# Markovic_Mario.net
KiCad netlist of a schematic drawn in Altium Designer
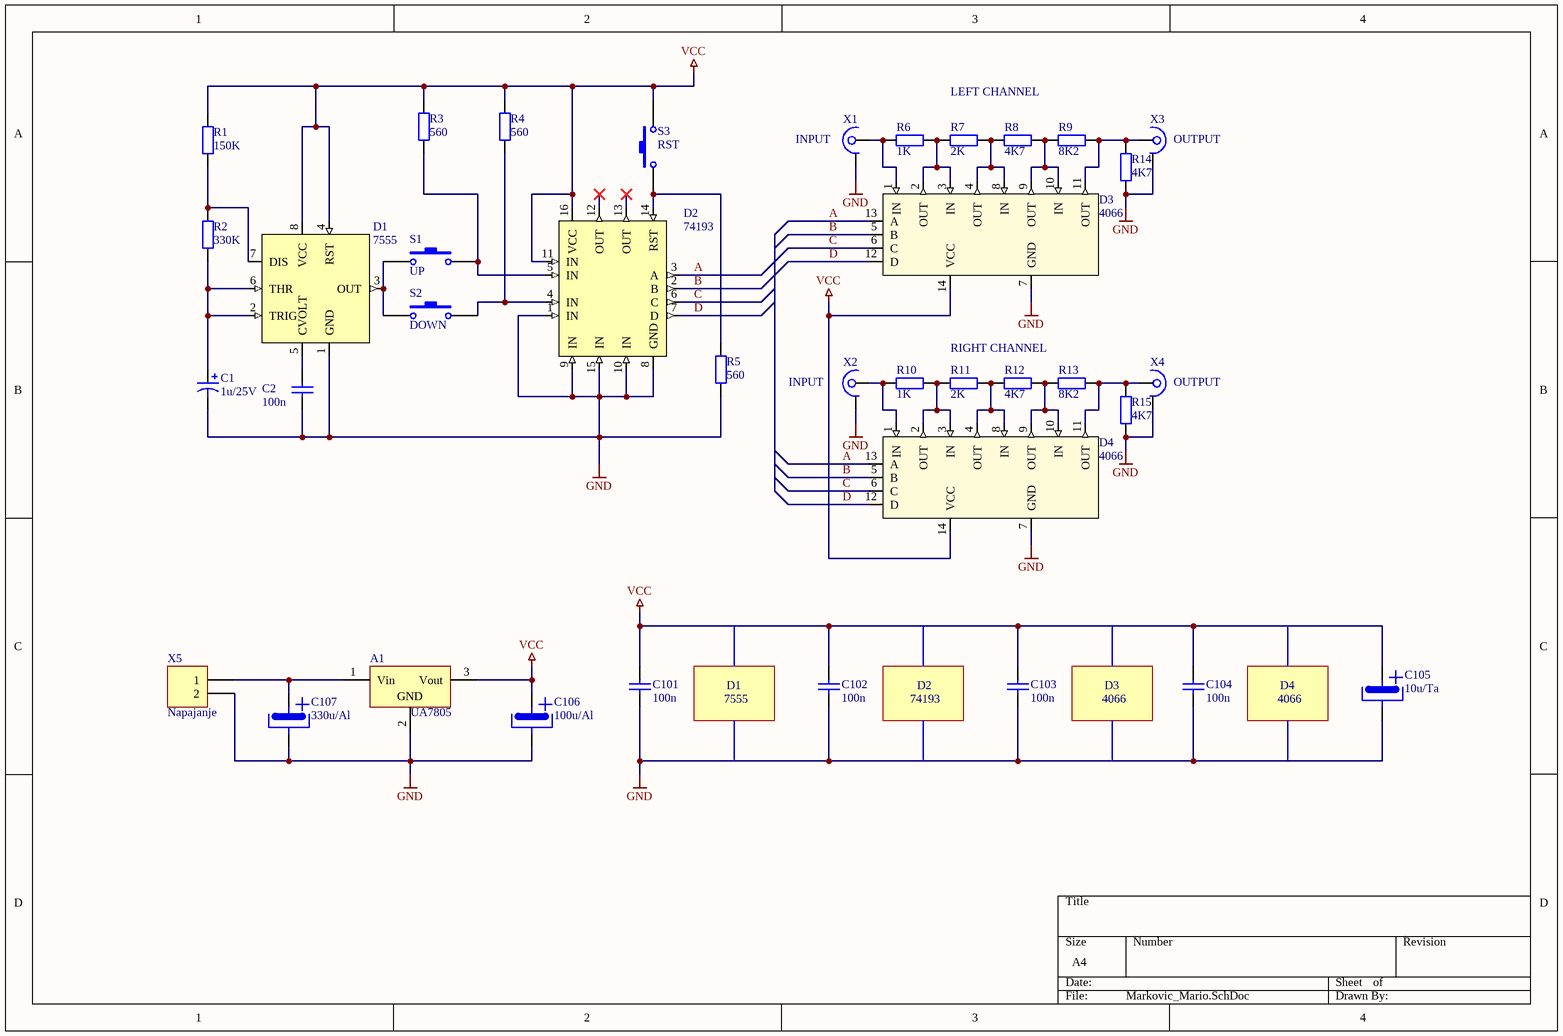
[diagram p0: Markovic_Mario.SchDoc]

(export (version "E")
  (design (tool "Eeschema 10.0.6"))
  (components
    (comp (ref "A1")
      (value "UA7805")
      (footprint "TO-220AB")
      (description "Voltage Regulator")
      (libsource (lib "Miscellaneous Devices") (part "Volt Reg"))
    )
    (comp (ref "C1")
      (value "1u/25V")
      (footprint "RB7.6-15")
      (description "Polarized Capacitor (Radial)")
      (libsource (lib "Miscellaneous Devices") (part "Cap Pol1"))
    )
    (comp (ref "C2")
      (value "100n")
      (footprint "RAD-0.3")
      (description "Capacitor")
      (libsource (lib "Miscellaneous Devices") (part "Cap"))
    )
    (comp (ref "C101")
      (value "100n")
      (footprint "RAD-0.3")
      (description "Capacitor")
      (libsource (lib "Miscellaneous Devices") (part "Cap"))
    )
    (comp (ref "C102")
      (value "100n")
      (footprint "RAD-0.3")
      (description "Capacitor")
      (libsource (lib "Miscellaneous Devices") (part "Cap"))
    )
    (comp (ref "C103")
      (value "100n")
      (footprint "RAD-0.3")
      (description "Capacitor")
      (libsource (lib "Miscellaneous Devices") (part "Cap"))
    )
    (comp (ref "C104")
      (value "100n")
      (footprint "RAD-0.3")
      (description "Capacitor")
      (libsource (lib "Miscellaneous Devices") (part "Cap"))
    )
    (comp (ref "C105")
      (value "10u/Ta")
      (footprint "RB7.6-15")
      (libsource (lib "Markovic_Mario") (part "Elektrolitski kondenzator"))
    )
    (comp (ref "C106")
      (value "100u/Al")
      (footprint "RB7.6-15")
      (libsource (lib "Markovic_Mario") (part "Elektrolitski kondenzator"))
    )
    (comp (ref "C107")
      (value "330u/Al")
      (footprint "RB7.6-15")
      (libsource (lib "Markovic_Mario") (part "Elektrolitski kondenzator"))
    )
    (comp (ref "D1") (value "7555") (footprint "DIP-8") (libsource (lib "Markovic_Mario") (part "7555")))
    (comp (ref "D2") (value "74193") (footprint "DIP-16") (libsource (lib "Markovic_Mario") (part "74193")))
    (comp (ref "D3") (value "4066") (footprint "DIP-14") (libsource (lib "Markovic_Mario") (part "4066")))
    (comp (ref "D4") (value "4066") (footprint "DIP-14") (libsource (lib "Markovic_Mario") (part "4066")))
    (comp (ref "R1")
      (value "150K")
      (footprint "AXIAL-0.4")
      (description "Resistor")
      (libsource (lib "") (part "Res2_1"))
    )
    (comp (ref "R2")
      (value "330K")
      (footprint "AXIAL-0.4")
      (description "Resistor")
      (libsource (lib "Miscellaneous Devices") (part "Res2"))
    )
    (comp (ref "R3")
      (value "560")
      (footprint "AXIAL-0.4")
      (description "Resistor")
      (libsource (lib "Miscellaneous Devices") (part "Res2"))
    )
    (comp (ref "R4")
      (value "560")
      (footprint "AXIAL-0.4")
      (description "Resistor")
      (libsource (lib "Miscellaneous Devices") (part "Res2"))
    )
    (comp (ref "R5")
      (value "560")
      (footprint "AXIAL-0.4")
      (description "Resistor")
      (libsource (lib "Miscellaneous Devices") (part "Res2"))
    )
    (comp (ref "R6")
      (value "1K")
      (footprint "AXIAL-0.4")
      (description "Resistor")
      (libsource (lib "") (part "Res2_2"))
    )
    (comp (ref "R7")
      (value "2K")
      (footprint "AXIAL-0.4")
      (description "Resistor")
      (libsource (lib "") (part "Res2_2"))
    )
    (comp (ref "R8")
      (value "4K7")
      (footprint "AXIAL-0.4")
      (description "Resistor")
      (libsource (lib "") (part "Res2_2"))
    )
    (comp (ref "R9")
      (value "8K2")
      (footprint "AXIAL-0.4")
      (description "Resistor")
      (libsource (lib "") (part "Res2_2"))
    )
    (comp (ref "R10")
      (value "1K")
      (footprint "AXIAL-0.4")
      (description "Resistor")
      (libsource (lib "") (part "Res2_2"))
    )
    (comp (ref "R11")
      (value "2K")
      (footprint "AXIAL-0.4")
      (description "Resistor")
      (libsource (lib "") (part "Res2_2"))
    )
    (comp (ref "R12")
      (value "4K7")
      (footprint "AXIAL-0.4")
      (description "Resistor")
      (libsource (lib "") (part "Res2_2"))
    )
    (comp (ref "R13")
      (value "8K2")
      (footprint "AXIAL-0.4")
      (description "Resistor")
      (libsource (lib "") (part "Res2_2"))
    )
    (comp (ref "R14")
      (value "4K7")
      (footprint "AXIAL-0.4")
      (description "Resistor")
      (libsource (lib "Miscellaneous Devices") (part "Res2"))
    )
    (comp (ref "R15")
      (value "4K7")
      (footprint "AXIAL-0.4")
      (description "Resistor")
      (libsource (lib "Miscellaneous Devices") (part "Res2"))
    )
    (comp (ref "S1")
      (value "UP")
      (footprint "SWITCH")
      (description "Switch")
      (libsource (lib "Miscellaneous Devices") (part "SW-PB"))
    )
    (comp (ref "S2")
      (value "DOWN")
      (footprint "SWITCH")
      (description "Switch")
      (libsource (lib "Miscellaneous Devices") (part "SW-PB"))
    )
    (comp (ref "S3")
      (value "RST")
      (footprint "SWITCH")
      (description "Switch")
      (libsource (lib "Miscellaneous Devices") (part "SW-PB"))
    )
    (comp (ref "X1") (value "INPUT") (footprint "JACK") (libsource (lib "Markovic_Mario") (part "Konektor")))
    (comp (ref "X2") (value "INPUT") (footprint "JACK") (libsource (lib "Markovic_Mario") (part "Konektor")))
    (comp (ref "X3") (value "OUTPUT") (footprint "JACK") (libsource (lib "") (part "Konektor_1")))
    (comp (ref "X4") (value "OUTPUT") (footprint "JACK") (libsource (lib "") (part "Konektor_1")))
    (comp (ref "X5")
      (value "Napajanje")
      (footprint "BAT-2")
      (description "Header, 2-Pin")
      (libsource (lib "Miscellaneous Connectors") (part "Header 2"))
    )
  )
  (nets
    (net (code "1") (name "/A") (class "Default")
      (node (ref "D2") (pin "3") (pinfunction "A_3") (pintype "output"))
      (node (ref "D3") (pin "13") (pinfunction "A_13") (pintype "passive"))
      (node (ref "D4") (pin "13") (pinfunction "A_13") (pintype "passive"))
    )
    (net (code "2") (name "/B") (class "Default")
      (node (ref "D2") (pin "2") (pinfunction "B_2") (pintype "output"))
      (node (ref "D3") (pin "5") (pinfunction "B_5") (pintype "passive"))
      (node (ref "D4") (pin "5") (pinfunction "B_5") (pintype "passive"))
    )
    (net (code "3") (name "/C") (class "Default")
      (node (ref "D2") (pin "6") (pinfunction "C_6") (pintype "output"))
      (node (ref "D3") (pin "6") (pinfunction "C_6") (pintype "passive"))
      (node (ref "D4") (pin "6") (pinfunction "C_6") (pintype "passive"))
    )
    (net (code "4") (name "/D") (class "Default")
      (node (ref "D2") (pin "7") (pinfunction "D_7") (pintype "output"))
      (node (ref "D3") (pin "12") (pinfunction "D_12") (pintype "passive"))
      (node (ref "D4") (pin "12") (pinfunction "D_12") (pintype "passive"))
    )
    (net (code "5") (name "GND") (class "Default")
      (node (ref "A1") (pin "2") (pinfunction "GND_2") (pintype "passive"))
      (node (ref "C1") (pin "2") (pinfunction "2_2") (pintype "passive"))
      (node (ref "C101") (pin "1") (pinfunction "1_1") (pintype "passive"))
      (node (ref "C102") (pin "1") (pinfunction "1_1") (pintype "passive"))
      (node (ref "C103") (pin "1") (pinfunction "1_1") (pintype "passive"))
      (node (ref "C104") (pin "1") (pinfunction "1_1") (pintype "passive"))
      (node (ref "C105") (pin "2") (pinfunction "2_2") (pintype "passive"))
      (node (ref "C106") (pin "2") (pinfunction "2_2") (pintype "passive"))
      (node (ref "C107") (pin "2") (pinfunction "2_2") (pintype "passive"))
      (node (ref "C2") (pin "1") (pinfunction "1_1") (pintype "passive"))
      (node (ref "D1") (pin "1") (pinfunction "GND_1") (pintype "power_in"))
      (node (ref "D2") (pin "1") (pinfunction "IN_1") (pintype "input"))
      (node (ref "D2") (pin "10") (pinfunction "IN_10") (pintype "input"))
      (node (ref "D2") (pin "15") (pinfunction "IN_15") (pintype "input"))
      (node (ref "D2") (pin "8") (pinfunction "GND_8") (pintype "power_in"))
      (node (ref "D2") (pin "9") (pinfunction "IN_9") (pintype "input"))
      (node (ref "D3") (pin "7") (pinfunction "GND_7") (pintype "power_in"))
      (node (ref "D4") (pin "7") (pinfunction "GND_7") (pintype "power_in"))
      (node (ref "R14") (pin "1") (pinfunction "1_1") (pintype "passive"))
      (node (ref "R15") (pin "1") (pinfunction "1_1") (pintype "passive"))
      (node (ref "R5") (pin "1") (pinfunction "1_1") (pintype "passive"))
      (node (ref "X1") (pin "2") (pinfunction "2_2") (pintype "passive"))
      (node (ref "X2") (pin "2") (pinfunction "2_2") (pintype "passive"))
      (node (ref "X3") (pin "2") (pinfunction "2_2") (pintype "passive"))
      (node (ref "X4") (pin "2") (pinfunction "2_2") (pintype "passive"))
      (node (ref "X5") (pin "2") (pinfunction "2_2") (pintype "passive"))
    )
    (net (code "6") (name "Net-(A1-Vin)") (class "Default")
      (node (ref "A1") (pin "1") (pinfunction "Vin_1") (pintype "passive"))
      (node (ref "C107") (pin "1") (pinfunction "1_1") (pintype "passive"))
      (node (ref "X5") (pin "1") (pinfunction "1_1") (pintype "passive"))
    )
    (net (code "7") (name "Net-(D1-CVOLT)") (class "Default")
      (node (ref "C2") (pin "2") (pinfunction "2_2") (pintype "passive"))
      (node (ref "D1") (pin "5") (pinfunction "CVOLT_5") (pintype "passive"))
    )
    (net (code "8") (name "Net-(D1-DIS)") (class "Default")
      (node (ref "D1") (pin "7") (pinfunction "DIS_7") (pintype "passive"))
      (node (ref "R1") (pin "2") (pinfunction "2_2") (pintype "passive"))
      (node (ref "R2") (pin "2") (pinfunction "2_2") (pintype "passive"))
    )
    (net (code "9") (name "Net-(D1-OUT)") (class "Default")
      (node (ref "D1") (pin "3") (pinfunction "OUT_3") (pintype "output"))
      (node (ref "S1") (pin "1") (pinfunction "1_1") (pintype "passive"))
      (node (ref "S2") (pin "1") (pinfunction "1_1") (pintype "passive"))
    )
    (net (code "10") (name "Net-(D1-THR)") (class "Default")
      (node (ref "C1") (pin "1") (pinfunction "1_1") (pintype "passive"))
      (node (ref "D1") (pin "2") (pinfunction "TRIG_2") (pintype "input"))
      (node (ref "D1") (pin "6") (pinfunction "THR_6") (pintype "input"))
      (node (ref "R2") (pin "1") (pinfunction "1_1") (pintype "passive"))
    )
    (net (code "11") (name "Net-(D2-IN-Pad4)") (class "Default")
      (node (ref "D2") (pin "4") (pinfunction "IN_4") (pintype "input"))
      (node (ref "R4") (pin "1") (pinfunction "1_1") (pintype "passive"))
      (node (ref "S2") (pin "2") (pinfunction "2_2") (pintype "passive"))
    )
    (net (code "12") (name "Net-(D2-IN-Pad5)") (class "Default")
      (node (ref "D2") (pin "5") (pinfunction "IN_5") (pintype "input"))
      (node (ref "R3") (pin "1") (pinfunction "1_1") (pintype "passive"))
      (node (ref "S1") (pin "2") (pinfunction "2_2") (pintype "passive"))
    )
    (net (code "13") (name "Net-(D2-RST)") (class "Default")
      (node (ref "D2") (pin "14") (pinfunction "RST_14") (pintype "input"))
      (node (ref "R5") (pin "2") (pinfunction "2_2") (pintype "passive"))
      (node (ref "S3") (pin "1") (pinfunction "1_1") (pintype "passive"))
    )
    (net (code "14") (name "Net-(D3-IN-Pad1)") (class "Default")
      (node (ref "D3") (pin "1") (pinfunction "IN_1") (pintype "input"))
      (node (ref "R6") (pin "2") (pinfunction "2_2") (pintype "passive"))
      (node (ref "X1") (pin "1") (pinfunction "1_1") (pintype "passive"))
    )
    (net (code "15") (name "Net-(D3-IN-Pad3)") (class "Default")
      (node (ref "D3") (pin "2") (pinfunction "OUT_2") (pintype "output"))
      (node (ref "D3") (pin "3") (pinfunction "IN_3") (pintype "input"))
      (node (ref "R6") (pin "1") (pinfunction "1_1") (pintype "passive"))
      (node (ref "R7") (pin "2") (pinfunction "2_2") (pintype "passive"))
    )
    (net (code "16") (name "Net-(D3-IN-Pad8)") (class "Default")
      (node (ref "D3") (pin "4") (pinfunction "OUT_4") (pintype "output"))
      (node (ref "D3") (pin "8") (pinfunction "IN_8") (pintype "input"))
      (node (ref "R7") (pin "1") (pinfunction "1_1") (pintype "passive"))
      (node (ref "R8") (pin "2") (pinfunction "2_2") (pintype "passive"))
    )
    (net (code "17") (name "Net-(D3-IN-Pad10)") (class "Default")
      (node (ref "D3") (pin "10") (pinfunction "IN_10") (pintype "input"))
      (node (ref "D3") (pin "9") (pinfunction "OUT_9") (pintype "output"))
      (node (ref "R8") (pin "1") (pinfunction "1_1") (pintype "passive"))
      (node (ref "R9") (pin "2") (pinfunction "2_2") (pintype "passive"))
    )
    (net (code "18") (name "Net-(D3-OUT-Pad11)") (class "Default")
      (node (ref "D3") (pin "11") (pinfunction "OUT_11") (pintype "output"))
      (node (ref "R14") (pin "2") (pinfunction "2_2") (pintype "passive"))
      (node (ref "R9") (pin "1") (pinfunction "1_1") (pintype "passive"))
      (node (ref "X3") (pin "1") (pinfunction "1_1") (pintype "passive"))
    )
    (net (code "19") (name "Net-(D4-IN-Pad1)") (class "Default")
      (node (ref "D4") (pin "1") (pinfunction "IN_1") (pintype "input"))
      (node (ref "R10") (pin "2") (pinfunction "2_2") (pintype "passive"))
      (node (ref "X2") (pin "1") (pinfunction "1_1") (pintype "passive"))
    )
    (net (code "20") (name "Net-(D4-IN-Pad3)") (class "Default")
      (node (ref "D4") (pin "2") (pinfunction "OUT_2") (pintype "output"))
      (node (ref "D4") (pin "3") (pinfunction "IN_3") (pintype "input"))
      (node (ref "R10") (pin "1") (pinfunction "1_1") (pintype "passive"))
      (node (ref "R11") (pin "2") (pinfunction "2_2") (pintype "passive"))
    )
    (net (code "21") (name "Net-(D4-IN-Pad8)") (class "Default")
      (node (ref "D4") (pin "4") (pinfunction "OUT_4") (pintype "output"))
      (node (ref "D4") (pin "8") (pinfunction "IN_8") (pintype "input"))
      (node (ref "R11") (pin "1") (pinfunction "1_1") (pintype "passive"))
      (node (ref "R12") (pin "2") (pinfunction "2_2") (pintype "passive"))
    )
    (net (code "22") (name "Net-(D4-IN-Pad10)") (class "Default")
      (node (ref "D4") (pin "10") (pinfunction "IN_10") (pintype "input"))
      (node (ref "D4") (pin "9") (pinfunction "OUT_9") (pintype "output"))
      (node (ref "R12") (pin "1") (pinfunction "1_1") (pintype "passive"))
      (node (ref "R13") (pin "2") (pinfunction "2_2") (pintype "passive"))
    )
    (net (code "23") (name "Net-(D4-OUT-Pad11)") (class "Default")
      (node (ref "D4") (pin "11") (pinfunction "OUT_11") (pintype "output"))
      (node (ref "R13") (pin "1") (pinfunction "1_1") (pintype "passive"))
      (node (ref "R15") (pin "2") (pinfunction "2_2") (pintype "passive"))
      (node (ref "X4") (pin "1") (pinfunction "1_1") (pintype "passive"))
    )
    (net (code "24") (name "VCC") (class "Default")
      (node (ref "A1") (pin "3") (pinfunction "Vout_3") (pintype "passive"))
      (node (ref "C101") (pin "2") (pinfunction "2_2") (pintype "passive"))
      (node (ref "C102") (pin "2") (pinfunction "2_2") (pintype "passive"))
      (node (ref "C103") (pin "2") (pinfunction "2_2") (pintype "passive"))
      (node (ref "C104") (pin "2") (pinfunction "2_2") (pintype "passive"))
      (node (ref "C105") (pin "1") (pinfunction "1_1") (pintype "passive"))
      (node (ref "C106") (pin "1") (pinfunction "1_1") (pintype "passive"))
      (node (ref "D1") (pin "4") (pinfunction "RST_4") (pintype "input"))
      (node (ref "D1") (pin "8") (pinfunction "VCC_8") (pintype "power_in"))
      (node (ref "D2") (pin "11") (pinfunction "IN_11") (pintype "input"))
      (node (ref "D2") (pin "16") (pinfunction "VCC_16") (pintype "power_in"))
      (node (ref "D3") (pin "14") (pinfunction "VCC_14") (pintype "power_in"))
      (node (ref "D4") (pin "14") (pinfunction "VCC_14") (pintype "power_in"))
      (node (ref "R1") (pin "1") (pinfunction "1_1") (pintype "passive"))
      (node (ref "R3") (pin "2") (pinfunction "2_2") (pintype "passive"))
      (node (ref "R4") (pin "2") (pinfunction "2_2") (pintype "passive"))
      (node (ref "S3") (pin "2") (pinfunction "2_2") (pintype "passive"))
    )
    (net (code "25") (name "unconnected-(D2-OUT-Pad12)") (class "Default")
      (node (ref "D2") (pin "12") (pinfunction "OUT_12") (pintype "output+no_connect"))
    )
    (net (code "26") (name "unconnected-(D2-OUT-Pad13)") (class "Default")
      (node (ref "D2") (pin "13") (pinfunction "OUT_13") (pintype "output+no_connect"))
    )
  )
)
